# MultiColorLight.net
KiCad netlist of a schematic drawn in EAGLE
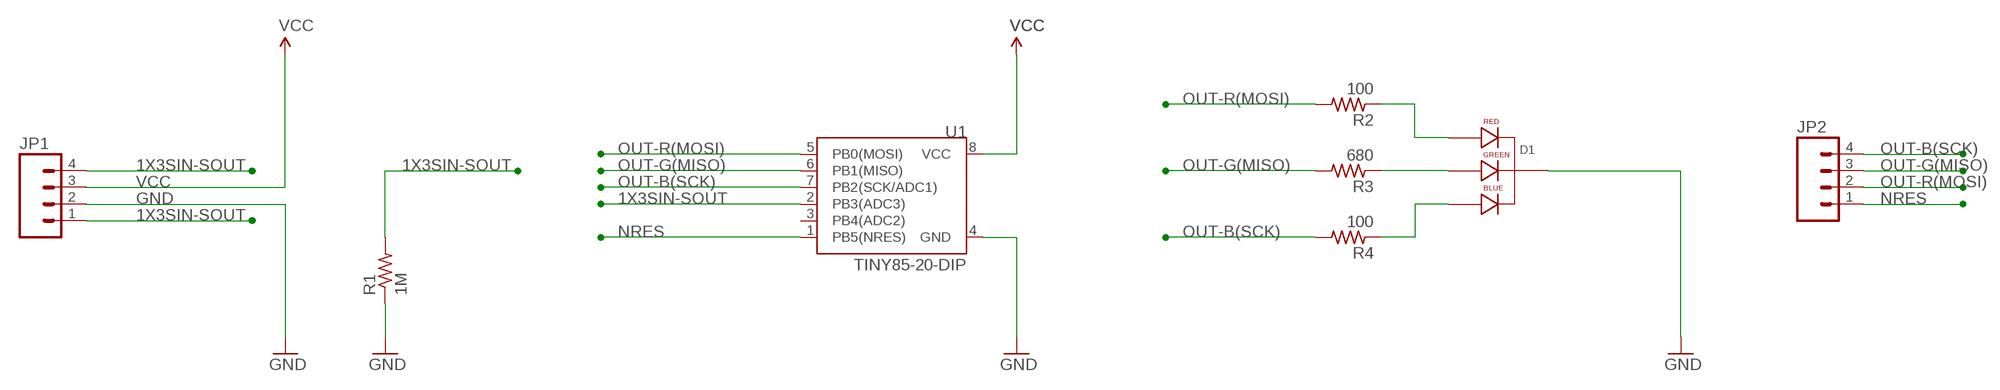
[diagram p0: schematic, sheet 1]

(export (version "E")
  (design (tool "Eeschema 10.0.6"))
  (components
    (comp (ref "D1")
      (value "LED-RGB-CC-THRUCLEAR")
      (footprint "eagle-import:LED-RGB-THRU")
      (libsource (lib "eagle-import") (part "LED-RGB-CC-THRUCLEAR"))
    )
    (comp (ref "JP1")
      (value "M04PTH")
      (footprint "eagle-import:1X04")
      (libsource (lib "eagle-import") (part "M04PTH"))
    )
    (comp (ref "JP2")
      (value "M04PTH")
      (footprint "eagle-import:1X04")
      (libsource (lib "eagle-import") (part "M04PTH"))
    )
    (comp (ref "R1")
      (value "1M")
      (footprint "eagle-import:R0603")
      (libsource (lib "eagle-import") (part "R-US_R0603"))
    )
    (comp (ref "R2")
      (value "100")
      (footprint "eagle-import:R0603")
      (libsource (lib "eagle-import") (part "R-US_R0603"))
    )
    (comp (ref "R3")
      (value "680")
      (footprint "eagle-import:R0603")
      (libsource (lib "eagle-import") (part "R-US_R0603"))
    )
    (comp (ref "R4")
      (value "100")
      (footprint "eagle-import:R0603")
      (libsource (lib "eagle-import") (part "R-US_R0603"))
    )
    (comp (ref "U1")
      (value "TINY85-20-DIP")
      (footprint "eagle-import:DIP08")
      (libsource (lib "eagle-import") (part "ATTINY45TINY85-20-DIP"))
    )
  )
  (nets
    (net (code "1") (name "/1X3SIN-SOUT") (class "Default")
      (node (ref "JP1") (pin "1") (pinfunction "1_1") (pintype "passive"))
      (node (ref "JP1") (pin "4") (pinfunction "4_4") (pintype "passive"))
      (node (ref "R1") (pin "2") (pinfunction "2_2") (pintype "passive"))
      (node (ref "U1") (pin "2") (pinfunction "PB3(ADC3)_2") (pintype "bidirectional"))
    )
    (net (code "2") (name "/NRES") (class "Default")
      (node (ref "JP2") (pin "1") (pinfunction "1_1") (pintype "passive"))
      (node (ref "U1") (pin "1") (pinfunction "PB5(NRES)_1") (pintype "bidirectional"))
    )
    (net (code "3") (name "/OUT-B(SCK)") (class "Default")
      (node (ref "JP2") (pin "4") (pinfunction "4_4") (pintype "passive"))
      (node (ref "R4") (pin "2") (pinfunction "2_2") (pintype "passive"))
      (node (ref "U1") (pin "7") (pinfunction "PB2(SCK/ADC1)_7") (pintype "bidirectional"))
    )
    (net (code "4") (name "/OUT-G(MISO)") (class "Default")
      (node (ref "JP2") (pin "3") (pinfunction "3_3") (pintype "passive"))
      (node (ref "R3") (pin "2") (pinfunction "2_2") (pintype "passive"))
      (node (ref "U1") (pin "6") (pinfunction "PB1(MISO)_6") (pintype "bidirectional"))
    )
    (net (code "5") (name "/OUT-R(MOSI)") (class "Default")
      (node (ref "JP2") (pin "2") (pinfunction "2_2") (pintype "passive"))
      (node (ref "R2") (pin "2") (pinfunction "2_2") (pintype "passive"))
      (node (ref "U1") (pin "5") (pinfunction "PB0(MOSI)_5") (pintype "bidirectional"))
    )
    (net (code "6") (name "GND") (class "Default")
      (node (ref "D1") (pin "2") (pinfunction "CATHODE_2") (pintype "bidirectional"))
      (node (ref "JP1") (pin "2") (pinfunction "2_2") (pintype "passive"))
      (node (ref "R1") (pin "1") (pinfunction "1_1") (pintype "passive"))
      (node (ref "U1") (pin "4") (pinfunction "GND_4") (pintype "bidirectional"))
    )
    (net (code "7") (name "Net-(D1-BLUE_CATHODE)") (class "Default")
      (node (ref "D1") (pin "4") (pinfunction "BLUE_CATHODE_4") (pintype "bidirectional"))
      (node (ref "R4") (pin "1") (pinfunction "1_1") (pintype "passive"))
    )
    (net (code "8") (name "Net-(D1-GREEN_CATHODE)") (class "Default")
      (node (ref "D1") (pin "3") (pinfunction "GREEN_CATHODE_3") (pintype "bidirectional"))
      (node (ref "R3") (pin "1") (pinfunction "1_1") (pintype "passive"))
    )
    (net (code "9") (name "Net-(D1-RED_CATHODE)") (class "Default")
      (node (ref "D1") (pin "1") (pinfunction "RED_CATHODE_1") (pintype "bidirectional"))
      (node (ref "R2") (pin "1") (pinfunction "1_1") (pintype "passive"))
    )
    (net (code "10") (name "VCC") (class "Default")
      (node (ref "JP1") (pin "3") (pinfunction "3_3") (pintype "passive"))
      (node (ref "U1") (pin "8") (pinfunction "VCC_8") (pintype "bidirectional"))
    )
    (net (code "11") (name "unconnected-(U1-PB4(ADC2)-Pad3)") (class "Default")
      (node (ref "U1") (pin "3") (pinfunction "PB4(ADC2)_3") (pintype "bidirectional"))
    )
  )
)
